# hbridge_3_0.net
KiCad netlist of a schematic drawn in EAGLE
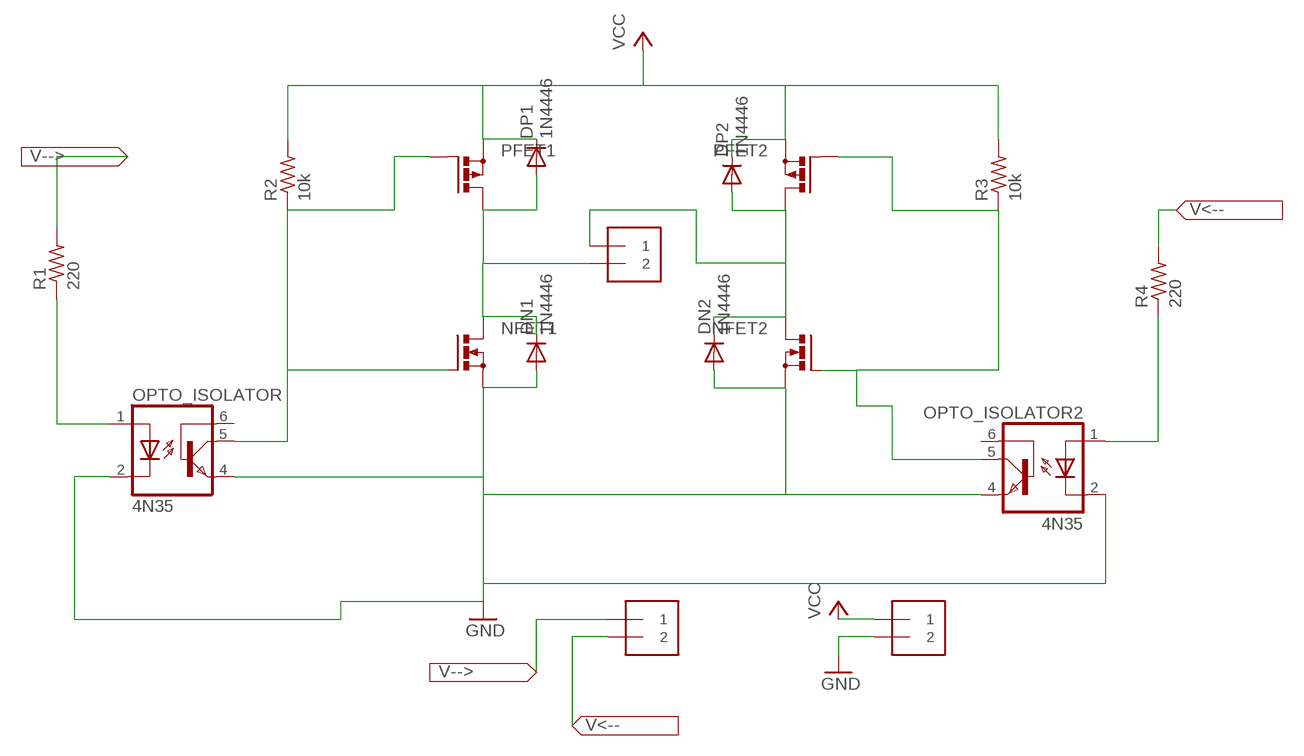
[diagram p0: schematic, sheet 1]

(export (version "E")
  (design (tool "Eeschema 10.0.6"))
  (components
    (comp (ref "ARDUINO")
      (value "1X2-3.5MM")
      (footprint "eagle-import:1X2-3.5MM")
      (libsource (lib "eagle-import") (part "1X2-3.5MM"))
    )
    (comp (ref "DN1")
      (value "1N4446")
      (footprint "eagle-import:DO35-10")
      (libsource (lib "eagle-import") (part "1N4446"))
    )
    (comp (ref "DN2")
      (value "1N4446")
      (footprint "eagle-import:DO35-10")
      (libsource (lib "eagle-import") (part "1N4446"))
    )
    (comp (ref "DP1")
      (value "1N4446")
      (footprint "eagle-import:DO35-10")
      (libsource (lib "eagle-import") (part "1N4446"))
    )
    (comp (ref "DP2")
      (value "1N4446")
      (footprint "eagle-import:DO35-10")
      (libsource (lib "eagle-import") (part "1N4446"))
    )
    (comp (ref "MOTOR")
      (value "1X2-3.5MM")
      (footprint "eagle-import:1X2-3.5MM")
      (libsource (lib "eagle-import") (part "1X2-3.5MM"))
    )
    (comp (ref "NFET1")
      (value "PMOSFET_NTO220BH")
      (footprint "eagle-import:TO220BH")
      (libsource (lib "eagle-import") (part "PMOSFET_NTO220BH"))
    )
    (comp (ref "NFET2")
      (value "PMOSFET_NTO220BH")
      (footprint "eagle-import:TO220BH")
      (libsource (lib "eagle-import") (part "PMOSFET_NTO220BH"))
    )
    (comp (ref "OPTO_ISOLATOR")
      (value "4N35")
      (footprint "eagle-import:DIL06")
      (fields (field (name "MF") "FAIRCHILD SEMICONDUCTOR"))
      (libsource (lib "eagle-import") (part "4N35"))
    )
    (comp (ref "OPTO_ISOLATOR2")
      (value "4N35")
      (footprint "eagle-import:DIL06")
      (fields (field (name "MF") "FAIRCHILD SEMICONDUCTOR"))
      (libsource (lib "eagle-import") (part "4N35"))
    )
    (comp (ref "PFET1")
      (value "PMOSFET_PTO220BH")
      (footprint "eagle-import:TO220BH")
      (libsource (lib "eagle-import") (part "PMOSFET_PTO220BH"))
    )
    (comp (ref "PFET2")
      (value "PMOSFET_PTO220BH")
      (footprint "eagle-import:TO220BH")
      (libsource (lib "eagle-import") (part "PMOSFET_PTO220BH"))
    )
    (comp (ref "POWER")
      (value "1X2-3.5MM")
      (footprint "eagle-import:1X2-3.5MM")
      (libsource (lib "eagle-import") (part "1X2-3.5MM"))
    )
    (comp (ref "R1")
      (value "220")
      (footprint "eagle-import:0207_15")
      (libsource (lib "eagle-import") (part "R-US_0207/15"))
    )
    (comp (ref "R2")
      (value "10k")
      (footprint "eagle-import:0207_15")
      (libsource (lib "eagle-import") (part "R-US_0207/15"))
    )
    (comp (ref "R3")
      (value "10k")
      (footprint "eagle-import:0207_15")
      (libsource (lib "eagle-import") (part "R-US_0207/15"))
    )
    (comp (ref "R4")
      (value "220")
      (footprint "eagle-import:0207_15")
      (libsource (lib "eagle-import") (part "R-US_0207/15"))
    )
  )
  (nets
    (net (code "1") (name "/ARDUINO_A") (class "Default")
      (node (ref "ARDUINO") (pin "1") (pinfunction "1_1") (pintype "passive"))
      (node (ref "R1") (pin "2") (pinfunction "2_2") (pintype "passive"))
    )
    (net (code "2") (name "/ARDUINO_B") (class "Default")
      (node (ref "ARDUINO") (pin "2") (pinfunction "2_2") (pintype "passive"))
      (node (ref "R4") (pin "2") (pinfunction "2_2") (pintype "passive"))
    )
    (net (code "3") (name "GND") (class "Default")
      (node (ref "DN1") (pin "A") (pinfunction "A_A") (pintype "passive"))
      (node (ref "DN2") (pin "A") (pinfunction "A_A") (pintype "passive"))
      (node (ref "NFET1") (pin "S") (pinfunction "S_S") (pintype "passive"))
      (node (ref "NFET2") (pin "S") (pinfunction "S_S") (pintype "passive"))
      (node (ref "OPTO_ISOLATOR") (pin "2") (pinfunction "C_2") (pintype "passive"))
      (node (ref "OPTO_ISOLATOR") (pin "4") (pinfunction "EMI_4") (pintype "passive"))
      (node (ref "OPTO_ISOLATOR2") (pin "2") (pinfunction "C_2") (pintype "passive"))
      (node (ref "OPTO_ISOLATOR2") (pin "4") (pinfunction "EMI_4") (pintype "passive"))
      (node (ref "POWER") (pin "2") (pinfunction "2_2") (pintype "passive"))
    )
    (net (code "4") (name "Net-(DN1-PadC)") (class "Default")
      (node (ref "DN1") (pin "C") (pinfunction "C_C") (pintype "passive"))
      (node (ref "DP1") (pin "A") (pinfunction "A_A") (pintype "passive"))
      (node (ref "MOTOR") (pin "2") (pinfunction "2_2") (pintype "passive"))
      (node (ref "NFET1") (pin "D") (pinfunction "D_D") (pintype "passive"))
      (node (ref "PFET1") (pin "D") (pinfunction "D_D") (pintype "passive"))
    )
    (net (code "5") (name "Net-(DN2-PadC)") (class "Default")
      (node (ref "DN2") (pin "C") (pinfunction "C_C") (pintype "passive"))
      (node (ref "DP2") (pin "A") (pinfunction "A_A") (pintype "passive"))
      (node (ref "MOTOR") (pin "1") (pinfunction "1_1") (pintype "passive"))
      (node (ref "NFET2") (pin "D") (pinfunction "D_D") (pintype "passive"))
      (node (ref "PFET2") (pin "D") (pinfunction "D_D") (pintype "passive"))
    )
    (net (code "6") (name "Net-(OPTO_ISOLATOR-A)") (class "Default")
      (node (ref "OPTO_ISOLATOR") (pin "1") (pinfunction "A_1") (pintype "passive"))
      (node (ref "R1") (pin "1") (pinfunction "1_1") (pintype "passive"))
    )
    (net (code "7") (name "Net-(OPTO_ISOLATOR-COL)") (class "Default")
      (node (ref "NFET1") (pin "G") (pinfunction "G_G") (pintype "passive"))
      (node (ref "OPTO_ISOLATOR") (pin "5") (pinfunction "COL_5") (pintype "passive"))
      (node (ref "PFET1") (pin "G") (pinfunction "G_G") (pintype "passive"))
      (node (ref "R2") (pin "1") (pinfunction "1_1") (pintype "passive"))
    )
    (net (code "8") (name "Net-(OPTO_ISOLATOR2-A)") (class "Default")
      (node (ref "OPTO_ISOLATOR2") (pin "1") (pinfunction "A_1") (pintype "passive"))
      (node (ref "R4") (pin "1") (pinfunction "1_1") (pintype "passive"))
    )
    (net (code "9") (name "Net-(OPTO_ISOLATOR2-COL)") (class "Default")
      (node (ref "NFET2") (pin "G") (pinfunction "G_G") (pintype "passive"))
      (node (ref "OPTO_ISOLATOR2") (pin "5") (pinfunction "COL_5") (pintype "passive"))
      (node (ref "PFET2") (pin "G") (pinfunction "G_G") (pintype "passive"))
      (node (ref "R3") (pin "1") (pinfunction "1_1") (pintype "passive"))
    )
    (net (code "10") (name "VCC") (class "Default")
      (node (ref "DP1") (pin "C") (pinfunction "C_C") (pintype "passive"))
      (node (ref "DP2") (pin "C") (pinfunction "C_C") (pintype "passive"))
      (node (ref "PFET1") (pin "S") (pinfunction "S_S") (pintype "passive"))
      (node (ref "PFET2") (pin "S") (pinfunction "S_S") (pintype "passive"))
      (node (ref "POWER") (pin "1") (pinfunction "1_1") (pintype "passive"))
      (node (ref "R2") (pin "2") (pinfunction "2_2") (pintype "passive"))
      (node (ref "R3") (pin "2") (pinfunction "2_2") (pintype "passive"))
    )
    (net (code "11") (name "unconnected-(OPTO_ISOLATOR-BAS-Pad6)") (class "Default")
      (node (ref "OPTO_ISOLATOR") (pin "6") (pinfunction "BAS_6") (pintype "passive"))
    )
    (net (code "12") (name "unconnected-(OPTO_ISOLATOR2-BAS-Pad6)") (class "Default")
      (node (ref "OPTO_ISOLATOR2") (pin "6") (pinfunction "BAS_6") (pintype "passive"))
    )
  )
)
